# DAC_Output_CH.net
KiCad netlist of a schematic drawn in Altium Designer
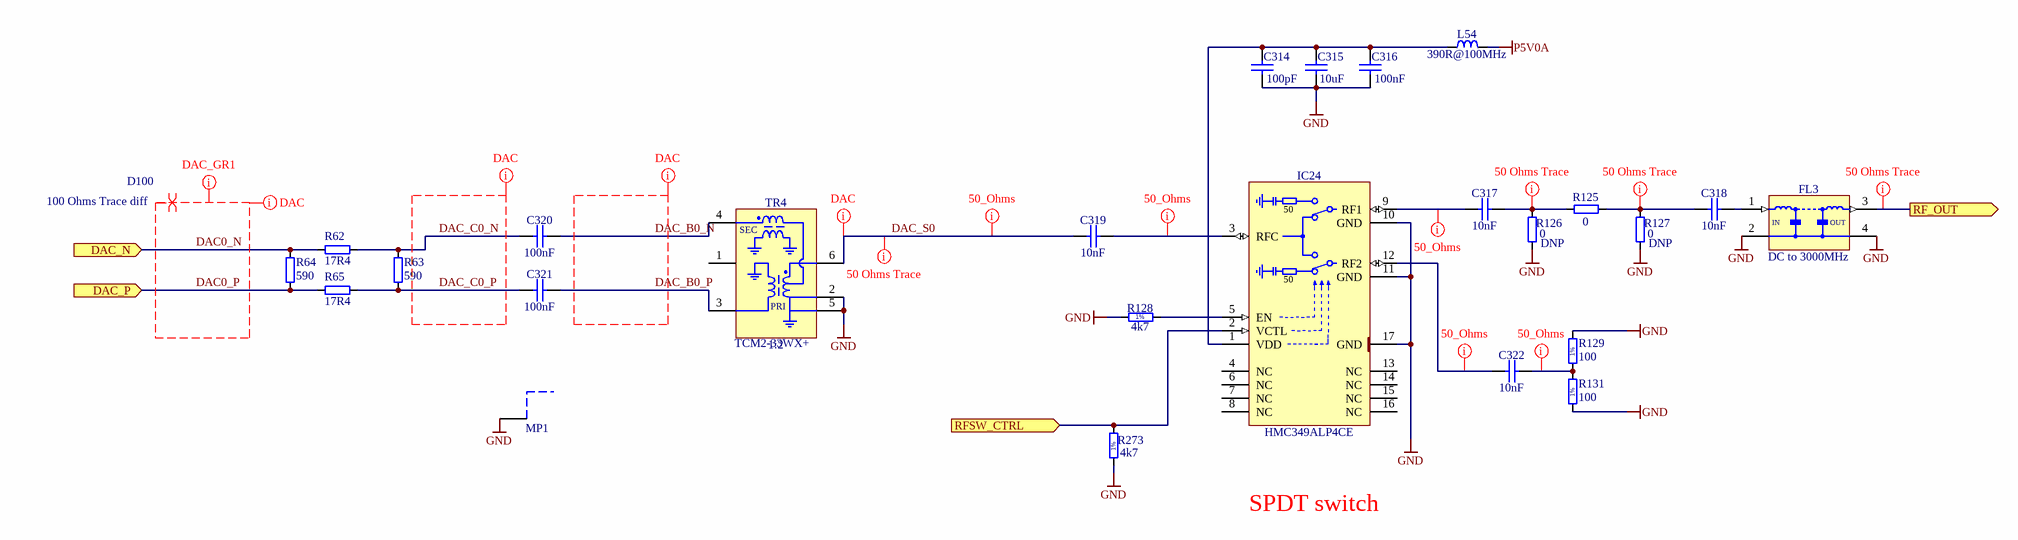
[diagram p0: DAC_Output_CH.SchDoc]

(export (version "E")
  (design (tool "Eeschema 10.0.6"))
  (components
    (comp (ref "C314")
      (value "100pF")
      (footprint "CAPC1005X55N")
      (description "Non-polarised capacitor")
      (fields
        (field (name "PART NUMBER") "CC0402_100PF_50V_5%_C0G")
        (field (name "VOLTAGE") "50V")
        (field (name "AUTHOR") "CERN DEM JLC")
      )
      (libsource (lib "Capacitors") (part "Capacitor - non polarized"))
    )
    (comp (ref "C315")
      (value "10uF")
      (footprint "CAPC1608X80N")
      (description "Non-polarised capacitor")
      (fields
        (field (name "PART NUMBER") "CC0603_10UF_16V_20%_X5R")
        (field (name "VOLTAGE") "16V")
        (field (name "AUTHOR") "CERN DEM MR")
      )
      (libsource (lib "Capacitors") (part "Capacitor - non polarized"))
    )
    (comp (ref "C316")
      (value "100nF")
      (footprint "CAPC1005X55N")
      (description "Non-polarised capacitor")
      (fields
        (field (name "PART NUMBER") "CC0402_100NF_16V_10%_X7R")
        (field (name "VOLTAGE") "16V")
        (field (name "AUTHOR") "CERN DEM JLC")
      )
      (libsource (lib "Capacitors") (part "Capacitor - non polarized"))
    )
    (comp (ref "C317")
      (value "10nF")
      (footprint "CAPC1005X55N")
      (description "Non-polarised capacitor")
      (fields
        (field (name "PART NUMBER") "CC0402_10NF_16V_10%_X7R")
        (field (name "VOLTAGE") "16V")
        (field (name "AUTHOR") "CERN DEM JLC")
      )
      (libsource (lib "Capacitors") (part "Capacitor - non polarized"))
    )
    (comp (ref "C318")
      (value "10nF")
      (footprint "CAPC1005X55N")
      (description "Non-polarised capacitor")
      (fields
        (field (name "PART NUMBER") "CC0402_10NF_16V_10%_X7R")
        (field (name "VOLTAGE") "16V")
        (field (name "AUTHOR") "CERN DEM JLC")
      )
      (libsource (lib "Capacitors") (part "Capacitor - non polarized"))
    )
    (comp (ref "C319")
      (value "10nF")
      (footprint "CAPC1005X55N")
      (description "Non-polarised capacitor")
      (fields
        (field (name "PART NUMBER") "CC0402_10NF_16V_10%_X7R")
        (field (name "VOLTAGE") "16V")
        (field (name "AUTHOR") "CERN DEM JLC")
      )
      (libsource (lib "Capacitors") (part "Capacitor - non polarized"))
    )
    (comp (ref "C320")
      (value "100nF")
      (footprint "CAPC0603X33N")
      (description "Non-polarised capacitor")
      (fields
        (field (name "PART NUMBER") "CC0201_100NF_6.3V_10%_X5R")
        (field (name "VOLTAGE") "6.3V")
        (field (name "AUTHOR") "CERN DEM JLC")
      )
      (libsource (lib "Capacitors") (part "Capacitor - non polarized"))
    )
    (comp (ref "C321")
      (value "100nF")
      (footprint "CAPC0603X33N")
      (description "Non-polarised capacitor")
      (fields
        (field (name "PART NUMBER") "CC0201_100NF_6.3V_10%_X5R")
        (field (name "VOLTAGE") "6.3V")
        (field (name "AUTHOR") "CERN DEM JLC")
      )
      (libsource (lib "Capacitors") (part "Capacitor - non polarized"))
    )
    (comp (ref "C322")
      (value "10nF")
      (footprint "CAPC1005X55N")
      (description "Non-polarised capacitor")
      (fields
        (field (name "PART NUMBER") "CC0402_10NF_16V_10%_X7R")
        (field (name "VOLTAGE") "16V")
        (field (name "AUTHOR") "CERN DEM JLC")
      )
      (libsource (lib "Capacitors") (part "Capacitor - non polarized"))
    )
    (comp (ref "FL3")
      (value "DC to 3000MHz")
      (footprint "FIL_MINI-CIRCUITS_FV1206")
      (description "50 Ohm Low Pass Filter")
      (fields
        (field (name "PART NUMBER") "FIL_MINI-CIRCUITS_LFCN-3000+")
        (field (name "MANUFACTURER") "MINI-CIRCUITS")
        (field (name "AUTHOR") "CERN DEM JLC")
      )
      (libsource (lib "Inductors & Transformers") (part "FIL_MINI-CIRCUITS_LFCN"))
    )
    (comp (ref "IC24")
      (value "HMC349ALP4CE")
      (footprint "QFN65P400X400X100-17N-S255")
      (description "DC-4GHz High Isolation SPDT Non-Reflective Switch")
      (fields (field (name "MANUFACTURER") "ANALOG DEVICES") (field (name "AUTHOR") "CERN DEM JLC"))
      (libsource (lib "ICs And Semiconductors") (part "HMC349ALP4CE"))
    )
    (comp (ref "L54")
      (value "390R@100MHz")
      (footprint "INDC1608X95N")
      (description "Inductor")
      (fields
        (field (name "PART NUMBER") "IND0603_TDK_MPZ1608R391A")
        (field (name "POWER") "1.2A")
        (field (name "AUTHOR") "CERN DEM JLC")
      )
      (libsource (lib "Inductors & Transformers") (part "Inductor"))
    )
    (comp (ref "MP1")
      (value "3670230")
      (footprint "3670230")
      (description "WE-SHC Shielding Cabinet, SMT Frame Seamless, Tin Plated, Tray, 23x11.7x5mm")
      (fields (field (name "MANUFACTURER") "Wurth Elektronik"))
      (libsource (lib "WE-SHC (rev22a)") (part "3670230"))
    )
    (comp (ref "R62")
      (value "17R4")
      (footprint "RESC1005X40N")
      (description "Resistor - 1%")
      (fields
        (field (name "TOLERANCE") "±1%")
        (field (name "VOLTAGE") "50V")
        (field (name "AUTHOR") "CERN DEM BC")
      )
      (libsource (lib "Resistors") (part "Resistor - 1%"))
    )
    (comp (ref "R63")
      (value "590")
      (footprint "RESC1005X40N")
      (description "Resistor - 1%")
      (fields
        (field (name "TOLERANCE") "±1%")
        (field (name "VOLTAGE") "50V")
        (field (name "AUTHOR") "CERN DEM BC")
      )
      (libsource (lib "Resistors") (part "Resistor - 1%"))
    )
    (comp (ref "R64")
      (value "590")
      (footprint "RESC1005X40N")
      (description "Resistor - 1%")
      (fields
        (field (name "TOLERANCE") "±1%")
        (field (name "VOLTAGE") "50V")
        (field (name "AUTHOR") "CERN DEM BC")
      )
      (libsource (lib "Resistors") (part "Resistor - 1%"))
    )
    (comp (ref "R65")
      (value "17R4")
      (footprint "RESC1005X40N")
      (description "Resistor - 1%")
      (fields
        (field (name "TOLERANCE") "±1%")
        (field (name "VOLTAGE") "50V")
        (field (name "AUTHOR") "CERN DEM BC")
      )
      (libsource (lib "Resistors") (part "Resistor - 1%"))
    )
    (comp (ref "R125")
      (value "0")
      (footprint "RESC1005X40N")
      (description "Resistor")
      (fields
        (field (name "PART NUMBER") "R0402_0R_JUMPER")
        (field (name "MANUFACTURER") "GENERIC")
        (field (name "AUTHOR") "CERN DEM JLC")
      )
      (libsource (lib "Resistors") (part "Resistor"))
    )
    (comp (ref "R126")
      (value "0")
      (footprint "RESC1005X40N")
      (description "Resistor")
      (fields
        (field (name "PART NUMBER") "R0402_0R_JUMPER")
        (field (name "MANUFACTURER") "GENERIC")
        (field (name "MOUNTED") "DNP")
        (field (name "AUTHOR") "CERN DEM JLC")
      )
      (libsource (lib "Resistors") (part "Resistor"))
    )
    (comp (ref "R127")
      (value "0")
      (footprint "RESC1005X40N")
      (description "Resistor")
      (fields
        (field (name "PART NUMBER") "R0402_0R_JUMPER")
        (field (name "MANUFACTURER") "GENERIC")
        (field (name "MOUNTED") "DNP")
        (field (name "AUTHOR") "CERN DEM JLC")
      )
      (libsource (lib "Resistors") (part "Resistor"))
    )
    (comp (ref "R128")
      (value "4k7")
      (footprint "RESC1005X40N")
      (description "Resistor - 1%")
      (fields
        (field (name "PART NUMBER") "R0402_4K7_1%_0.0625W_100PPM")
        (field (name "POWER") "0.0625W")
        (field (name "AUTHOR") "CERN DEM JLC")
      )
      (libsource (lib "Resistors") (part "Resistor - 1%"))
    )
    (comp (ref "R129")
      (value "100")
      (footprint "RESC1005X40N")
      (description "Resistor - 1%")
      (fields
        (field (name "PART NUMBER") "R0402_100R_1%_0.1W_100PPM")
        (field (name "POWER") "0.1W")
        (field (name "AUTHOR") "CERN DEM JLC")
      )
      (libsource (lib "Resistors") (part "Resistor - 1%"))
    )
    (comp (ref "R131")
      (value "100")
      (footprint "RESC1005X40N")
      (description "Resistor - 1%")
      (fields
        (field (name "PART NUMBER") "R0402_100R_1%_0.1W_100PPM")
        (field (name "POWER") "0.1W")
        (field (name "AUTHOR") "CERN DEM JLC")
      )
      (libsource (lib "Resistors") (part "Resistor - 1%"))
    )
    (comp (ref "R273")
      (value "4k7")
      (footprint "RESC1005X40N")
      (description "Resistor - 1%")
      (fields
        (field (name "PART NUMBER") "R0402_4K7_1%_0.0625W_100PPM")
        (field (name "POWER") "0.0625W")
        (field (name "AUTHOR") "CERN DEM JLC")
      )
      (libsource (lib "Resistors") (part "Resistor - 1%"))
    )
    (comp (ref "TR4")
      (value "1:2")
      (footprint "XFMR_MINI-CIRCUITS_DB1627")
      (description "50 OHMS 10 to 3000 MHz RF Transformer")
      (fields
        (field (name "PART NUMBER") "XFMR_MINI-CIRCUITS_TCM2-33WX+")
        (field (name "POWER") "0.4W")
        (field (name "MANUFACTURER PART NUMBER") "TCM2-33WX+")
        (field (name "AUTHOR") "CERN DEM MR")
      )
      (libsource (lib "Inductors & Transformers") (part "XFMR_MINI-CIRCUITS_TCM2-33WX+"))
    )
  )
  (nets
    (net (code "1") (name "/DAC0_N") (class "Default")
      (node (ref "R62") (pin "2") (pinfunction "2_2") (pintype "passive"))
      (node (ref "R64") (pin "1") (pinfunction "1_1") (pintype "passive"))
    )
    (net (code "2") (name "/DAC0_P") (class "Default")
      (node (ref "R64") (pin "2") (pinfunction "2_2") (pintype "passive"))
      (node (ref "R65") (pin "2") (pinfunction "2_2") (pintype "passive"))
    )
    (net (code "3") (name "/DAC_B0_N") (class "Default")
      (node (ref "C320") (pin "2") (pinfunction "2_2") (pintype "passive"))
      (node (ref "TR4") (pin "4") (pinfunction "SD_4") (pintype "passive"))
    )
    (net (code "4") (name "/DAC_B0_P") (class "Default")
      (node (ref "C321") (pin "2") (pinfunction "2_2") (pintype "passive"))
      (node (ref "TR4") (pin "3") (pinfunction "S_3") (pintype "passive"))
    )
    (net (code "5") (name "/DAC_C0_N") (class "Default")
      (node (ref "C320") (pin "1") (pinfunction "1_1") (pintype "passive"))
      (node (ref "R62") (pin "1") (pinfunction "1_1") (pintype "passive"))
      (node (ref "R63") (pin "1") (pinfunction "1_1") (pintype "passive"))
    )
    (net (code "6") (name "/DAC_C0_P") (class "Default")
      (node (ref "C321") (pin "1") (pinfunction "1_1") (pintype "passive"))
      (node (ref "R63") (pin "2") (pinfunction "2_2") (pintype "passive"))
      (node (ref "R65") (pin "1") (pinfunction "1_1") (pintype "passive"))
    )
    (net (code "7") (name "/DAC_S0") (class "Default")
      (node (ref "C319") (pin "1") (pinfunction "1_1") (pintype "passive"))
      (node (ref "TR4") (pin "6") (pinfunction "P1_6") (pintype "passive"))
    )
    (net (code "8") (name "/RFSW_CTRL") (class "Default")
      (node (ref "IC24") (pin "2") (pinfunction "VCTL_2") (pintype "input"))
      (node (ref "R273") (pin "2") (pinfunction "2_2") (pintype "passive"))
    )
    (net (code "9") (name "/RF_OUT") (class "Default")
      (node (ref "FL3") (pin "3") (pinfunction "RFOUT_3") (pintype "output"))
    )
    (net (code "10") (name "GND") (class "Default")
      (node (ref "C314") (pin "2") (pinfunction "2_2") (pintype "passive"))
      (node (ref "C315") (pin "1") (pinfunction "1_1") (pintype "passive"))
      (node (ref "C316") (pin "1") (pinfunction "1_1") (pintype "passive"))
      (node (ref "FL3") (pin "2") (pinfunction "GND_2") (pintype "power_in"))
      (node (ref "FL3") (pin "4") (pinfunction "GND_4") (pintype "power_in"))
      (node (ref "IC24") (pin "10") (pinfunction "GND_10") (pintype "power_in"))
      (node (ref "IC24") (pin "11") (pinfunction "GND_11") (pintype "power_in"))
      (node (ref "IC24") (pin "17") (pinfunction "GND_17") (pintype "power_in"))
      (node (ref "MP1") (pin "1") (pinfunction "1_1") (pintype "passive"))
      (node (ref "R126") (pin "1") (pinfunction "1_1") (pintype "passive"))
      (node (ref "R127") (pin "1") (pinfunction "1_1") (pintype "passive"))
      (node (ref "R128") (pin "1") (pinfunction "1_1") (pintype "passive"))
      (node (ref "R129") (pin "2") (pinfunction "2_2") (pintype "passive"))
      (node (ref "R131") (pin "1") (pinfunction "1_1") (pintype "passive"))
      (node (ref "R273") (pin "1") (pinfunction "1_1") (pintype "passive"))
      (node (ref "TR4") (pin "2") (pinfunction "P_2") (pintype "passive"))
      (node (ref "TR4") (pin "5") (pinfunction "GND_5") (pintype "power_in"))
    )
    (net (code "11") (name "Net-(C317-Pad2)") (class "Default")
      (node (ref "C317") (pin "2") (pinfunction "2_2") (pintype "passive"))
      (node (ref "R125") (pin "1") (pinfunction "1_1") (pintype "passive"))
      (node (ref "R126") (pin "2") (pinfunction "2_2") (pintype "passive"))
    )
    (net (code "12") (name "Net-(C318-Pad1)") (class "Default")
      (node (ref "C318") (pin "1") (pinfunction "1_1") (pintype "passive"))
      (node (ref "R125") (pin "2") (pinfunction "2_2") (pintype "passive"))
      (node (ref "R127") (pin "2") (pinfunction "2_2") (pintype "passive"))
    )
    (net (code "13") (name "Net-(C322-Pad2)") (class "Default")
      (node (ref "C322") (pin "2") (pinfunction "2_2") (pintype "passive"))
      (node (ref "R129") (pin "1") (pinfunction "1_1") (pintype "passive"))
      (node (ref "R131") (pin "2") (pinfunction "2_2") (pintype "passive"))
    )
    (net (code "14") (name "Net-(FL3-RFIN)") (class "Default")
      (node (ref "C318") (pin "2") (pinfunction "2_2") (pintype "passive"))
      (node (ref "FL3") (pin "1") (pinfunction "RFIN_1") (pintype "input"))
    )
    (net (code "15") (name "Net-(IC24-EN)") (class "Default")
      (node (ref "IC24") (pin "5") (pinfunction "EN_5") (pintype "input"))
      (node (ref "R128") (pin "2") (pinfunction "2_2") (pintype "passive"))
    )
    (net (code "16") (name "Net-(IC24-RF1)") (class "Default")
      (node (ref "C317") (pin "1") (pinfunction "1_1") (pintype "passive"))
      (node (ref "IC24") (pin "9") (pinfunction "RF1_9") (pintype "bidirectional"))
    )
    (net (code "17") (name "Net-(IC24-RF2)") (class "Default")
      (node (ref "C322") (pin "1") (pinfunction "1_1") (pintype "passive"))
      (node (ref "IC24") (pin "12") (pinfunction "RF2_12") (pintype "bidirectional"))
    )
    (net (code "18") (name "Net-(IC24-RFC)") (class "Default")
      (node (ref "C319") (pin "2") (pinfunction "2_2") (pintype "passive"))
      (node (ref "IC24") (pin "3") (pinfunction "RFC_3") (pintype "bidirectional"))
    )
    (net (code "19") (name "Net-(IC24-VDD)") (class "Default")
      (node (ref "C314") (pin "1") (pinfunction "1_1") (pintype "passive"))
      (node (ref "C315") (pin "2") (pinfunction "2_2") (pintype "passive"))
      (node (ref "C316") (pin "2") (pinfunction "2_2") (pintype "passive"))
      (node (ref "IC24") (pin "1") (pinfunction "VDD_1") (pintype "power_in"))
      (node (ref "L54") (pin "1") (pinfunction "1_1") (pintype "passive"))
    )
    (net (code "20") (name "P5V0A") (class "Default")
      (node (ref "L54") (pin "2") (pinfunction "2_2") (pintype "passive"))
    )
    (net (code "21") (name "unconnected-(IC24-NC-Pad4)") (class "Default")
      (node (ref "IC24") (pin "4") (pinfunction "NC_4") (pintype "passive"))
    )
    (net (code "22") (name "unconnected-(IC24-NC-Pad6)") (class "Default")
      (node (ref "IC24") (pin "6") (pinfunction "NC_6") (pintype "passive"))
    )
    (net (code "23") (name "unconnected-(IC24-NC-Pad7)") (class "Default")
      (node (ref "IC24") (pin "7") (pinfunction "NC_7") (pintype "passive"))
    )
    (net (code "24") (name "unconnected-(IC24-NC-Pad8)") (class "Default")
      (node (ref "IC24") (pin "8") (pinfunction "NC_8") (pintype "passive"))
    )
    (net (code "25") (name "unconnected-(IC24-NC-Pad13)") (class "Default")
      (node (ref "IC24") (pin "13") (pinfunction "NC_13") (pintype "passive"))
    )
    (net (code "26") (name "unconnected-(IC24-NC-Pad14)") (class "Default")
      (node (ref "IC24") (pin "14") (pinfunction "NC_14") (pintype "passive"))
    )
    (net (code "27") (name "unconnected-(IC24-NC-Pad15)") (class "Default")
      (node (ref "IC24") (pin "15") (pinfunction "NC_15") (pintype "passive"))
    )
    (net (code "28") (name "unconnected-(IC24-NC-Pad16)") (class "Default")
      (node (ref "IC24") (pin "16") (pinfunction "NC_16") (pintype "passive"))
    )
    (net (code "29") (name "unconnected-(TR4-NC-Pad1)") (class "Default")
      (node (ref "TR4") (pin "1") (pinfunction "NC_1") (pintype "passive"))
    )
  )
)
